# pcbCard.net
KiCad netlist of a schematic drawn in EAGLE
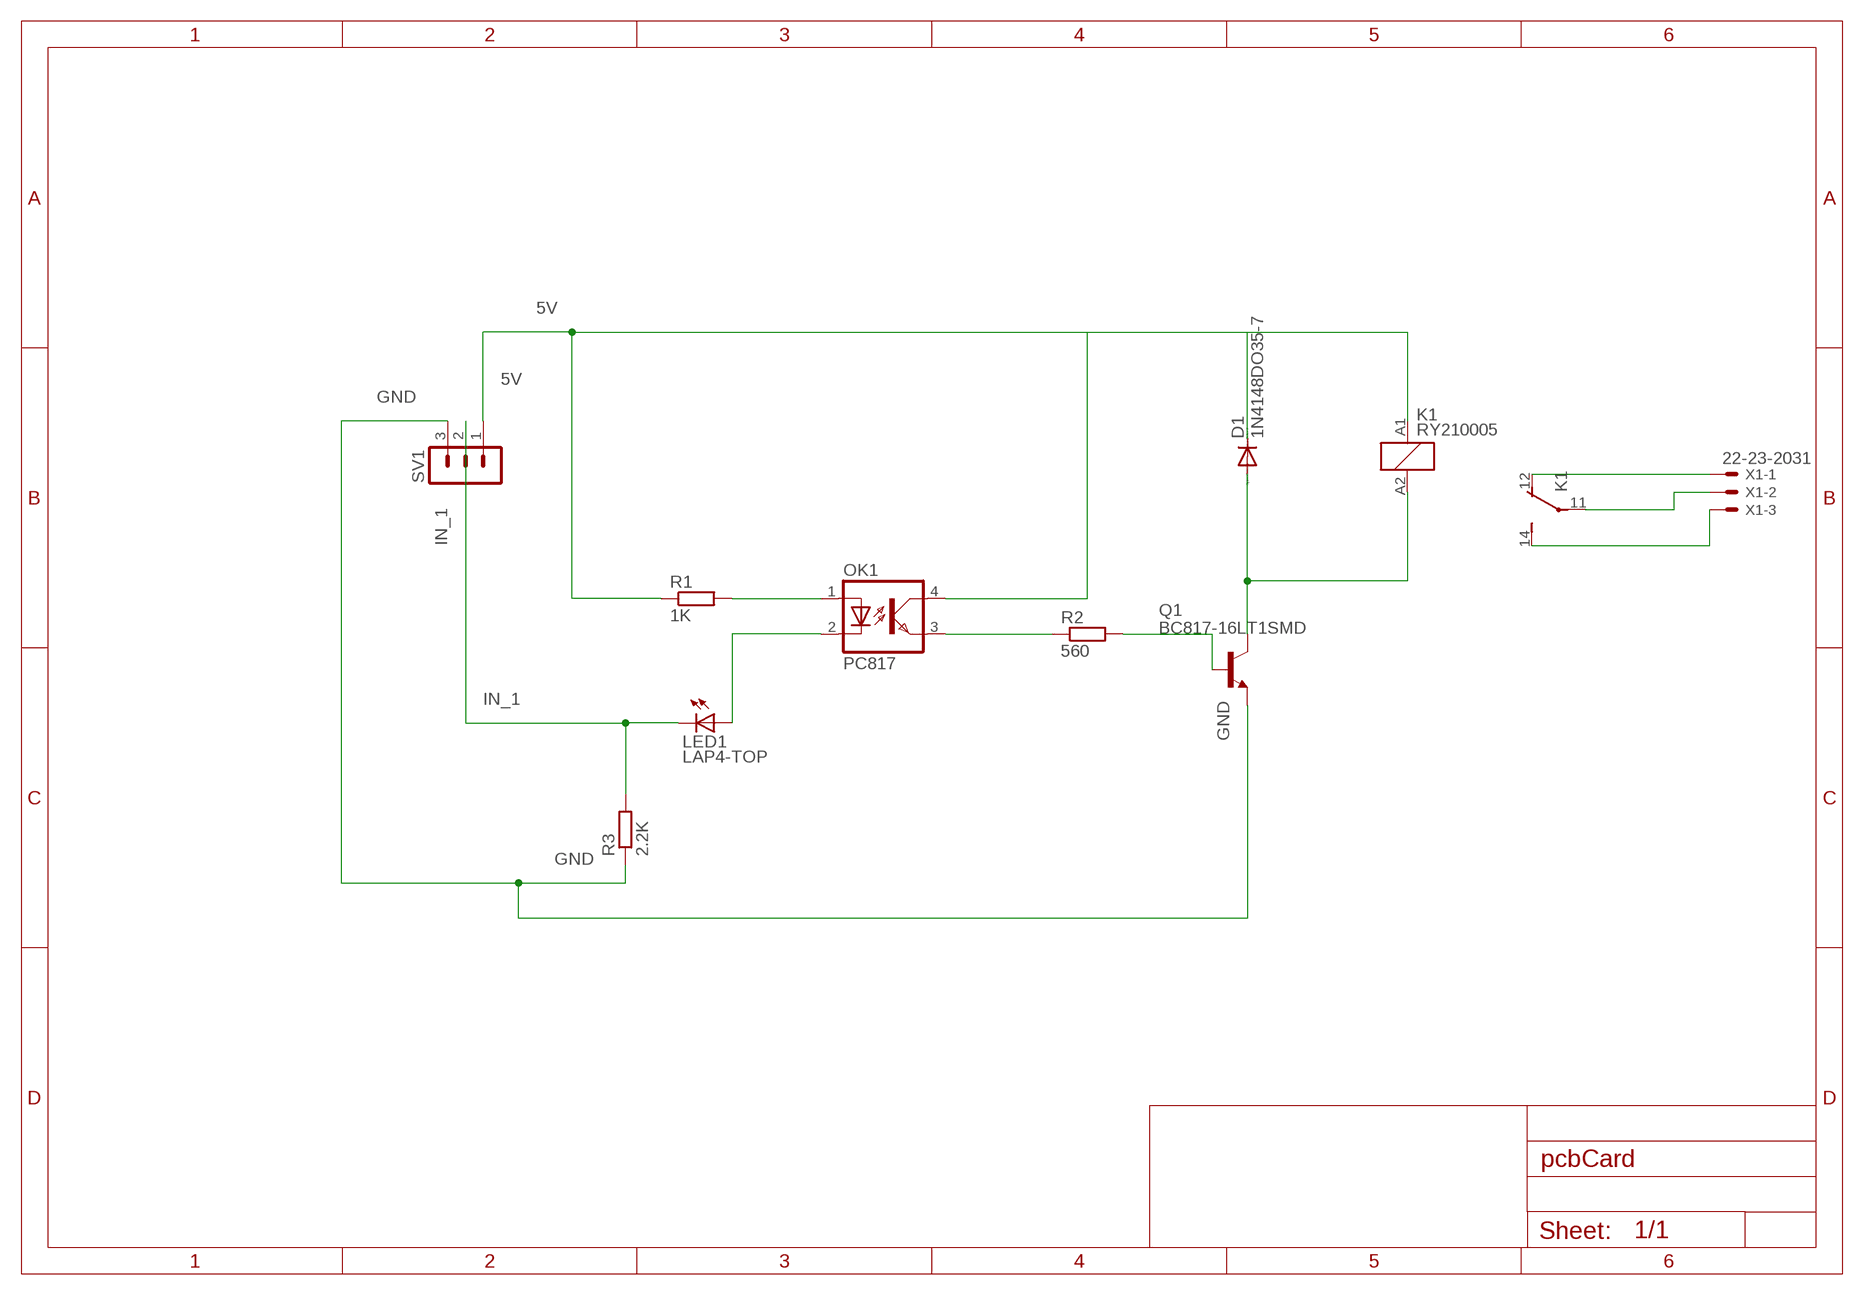
[diagram p0: schematic, sheet 1]

(export (version "E")
  (design (tool "Eeschema 10.0.6"))
  (components
    (comp (ref "D1")
      (value "1N4148DO35-7")
      (footprint "eagle-import:DO35-7")
      (libsource (lib "eagle-import") (part "1N4148DO35-7"))
    )
    (comp (ref "K1")
      (value "RY210005")
      (footprint "eagle-import:RY-II")
      (fields (field (name "MF") "TYCO ELECTRONICS"))
      (libsource (lib "eagle-import") (part "RY?120005"))
    )
    (comp (ref "LED1")
      (value "LAP4-TOP")
      (footprint "eagle-import:P47F-TOP")
      (libsource (lib "eagle-import") (part "P4-TOPLA"))
    )
    (comp (ref "OK1")
      (value "PC817")
      (footprint "eagle-import:DIL04")
      (fields (field (name "MPN") "PC817X4J000F"))
      (libsource (lib "eagle-import") (part "PC817"))
    )
    (comp (ref "Q1")
      (value "BC817-16LT1SMD")
      (footprint "eagle-import:SOT23-BEC")
      (libsource (lib "eagle-import") (part "BC817SMD-16LT1"))
    )
    (comp (ref "R1")
      (value "1K")
      (footprint "eagle-import:0204_5")
      (libsource (lib "eagle-import") (part "R-EU_0204/5"))
    )
    (comp (ref "R2")
      (value "560")
      (footprint "eagle-import:0204_5")
      (libsource (lib "eagle-import") (part "R-EU_0204/5"))
    )
    (comp (ref "R3")
      (value "2.2K")
      (footprint "eagle-import:0204_5")
      (libsource (lib "eagle-import") (part "R-EU_0204/5"))
    )
    (comp (ref "SV1")
      (value "MA03-1")
      (footprint "eagle-import:MA03-1")
      (libsource (lib "eagle-import") (part "MA03-1"))
    )
    (comp (ref "X1")
      (value "22-23-2031")
      (footprint "eagle-import:22-23-2031")
      (fields (field (name "MF") "MOLEX"))
      (libsource (lib "eagle-import") (part "22-23-2031"))
    )
  )
  (nets
    (net (code "1") (name "Net-(K1A-1)") (class "Default")
      (node (ref "D1") (pin "C") (pinfunction "C_C") (pintype "passive"))
      (node (ref "K1") (pin "A1") (pinfunction "1_A1") (pintype "passive"))
      (node (ref "OK1") (pin "4") (pinfunction "COL_4") (pintype "passive"))
      (node (ref "R1") (pin "1") (pinfunction "1_1") (pintype "passive"))
      (node (ref "SV1") (pin "1") (pinfunction "1_1") (pintype "passive"))
    )
    (net (code "2") (name "Net-(K1A-2)") (class "Default")
      (node (ref "D1") (pin "A") (pinfunction "A_A") (pintype "passive"))
      (node (ref "K1") (pin "A2") (pinfunction "2_A2") (pintype "passive"))
      (node (ref "Q1") (pin "C") (pinfunction "C_C") (pintype "passive"))
    )
    (net (code "3") (name "Net-(K1B-O)") (class "Default")
      (node (ref "K1") (pin "12") (pinfunction "O_12") (pintype "passive"))
      (node (ref "X1") (pin "1") (pinfunction "S_1") (pintype "passive"))
    )
    (net (code "4") (name "Net-(K1B-P)") (class "Default")
      (node (ref "K1") (pin "11") (pinfunction "P_11") (pintype "passive"))
      (node (ref "X1") (pin "2") (pinfunction "S_2") (pintype "passive"))
    )
    (net (code "5") (name "Net-(K1B-S)") (class "Default")
      (node (ref "K1") (pin "14") (pinfunction "S_14") (pintype "passive"))
      (node (ref "X1") (pin "3") (pinfunction "S_3") (pintype "passive"))
    )
    (net (code "6") (name "Net-(LED1-PadC)") (class "Default")
      (node (ref "LED1") (pin "C") (pinfunction "C_C") (pintype "passive"))
      (node (ref "R3") (pin "2") (pinfunction "2_2") (pintype "passive"))
      (node (ref "SV1") (pin "2") (pinfunction "2_2") (pintype "passive"))
    )
    (net (code "7") (name "Net-(OK1-A)") (class "Default")
      (node (ref "OK1") (pin "1") (pinfunction "A_1") (pintype "passive"))
      (node (ref "R1") (pin "2") (pinfunction "2_2") (pintype "passive"))
    )
    (net (code "8") (name "Net-(OK1-C)") (class "Default")
      (node (ref "LED1") (pin "A") (pinfunction "A_A") (pintype "passive"))
      (node (ref "OK1") (pin "2") (pinfunction "C_2") (pintype "passive"))
    )
    (net (code "9") (name "Net-(OK1-EMIT)") (class "Default")
      (node (ref "OK1") (pin "3") (pinfunction "EMIT_3") (pintype "passive"))
      (node (ref "R2") (pin "1") (pinfunction "1_1") (pintype "passive"))
    )
    (net (code "10") (name "Net-(Q1-PadB)") (class "Default")
      (node (ref "Q1") (pin "B") (pinfunction "B_B") (pintype "passive"))
      (node (ref "R2") (pin "2") (pinfunction "2_2") (pintype "passive"))
    )
    (net (code "11") (name "Net-(Q1-PadE)") (class "Default")
      (node (ref "Q1") (pin "E") (pinfunction "E_E") (pintype "passive"))
      (node (ref "R3") (pin "1") (pinfunction "1_1") (pintype "passive"))
      (node (ref "SV1") (pin "3") (pinfunction "3_3") (pintype "passive"))
    )
  )
)
